# shcV1.net
KiCad netlist of a schematic drawn in EAGLE
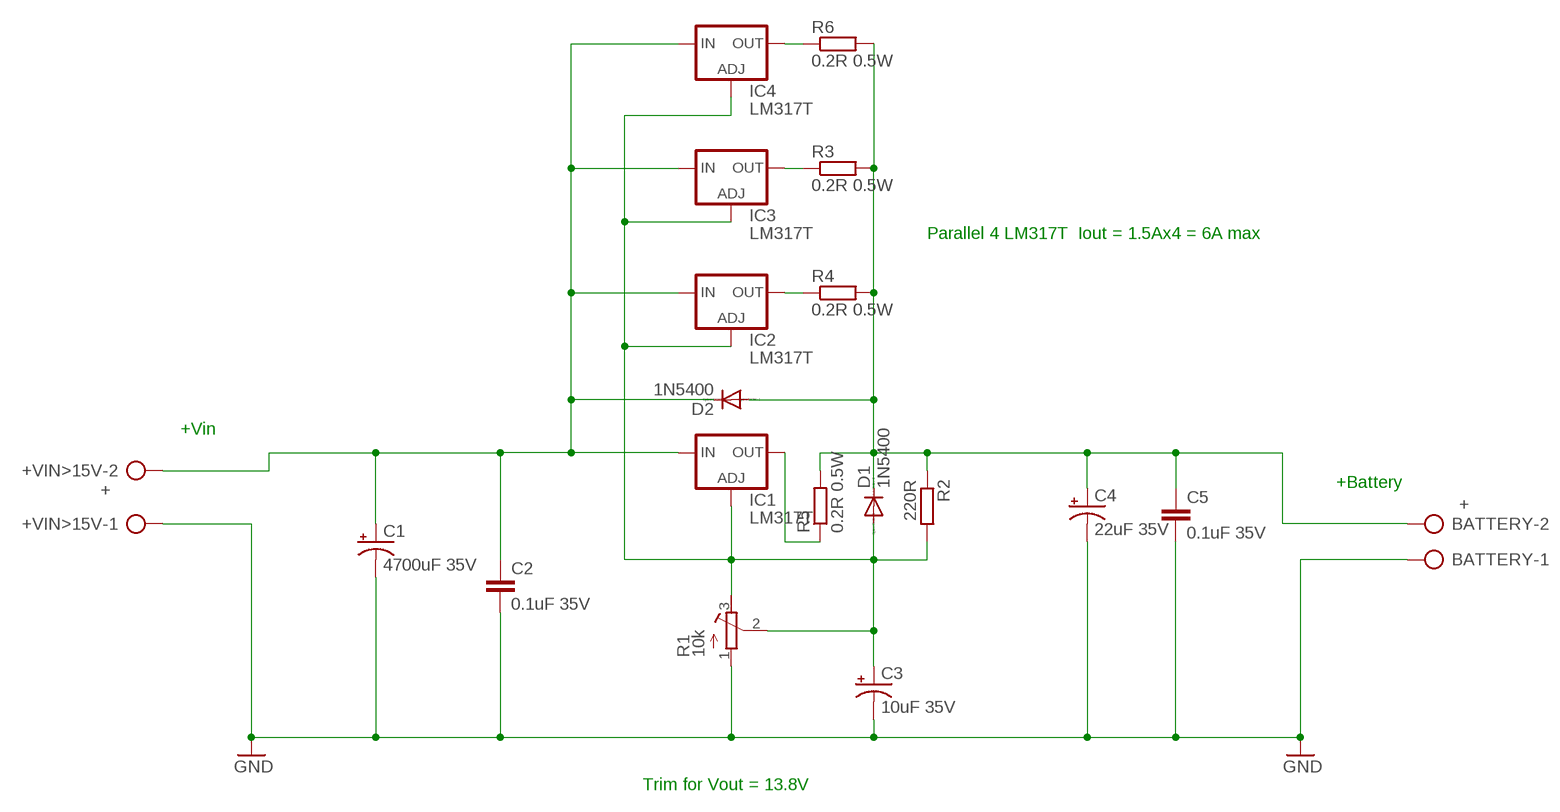
[diagram p0: schematic, sheet 1]

(export (version "E")
  (design (tool "Eeschema 10.0.6"))
  (components
    (comp (ref "+VIN>15V")
      (value "+")
      (footprint "eagle-import:AK300_2")
      (libsource (lib "eagle-import") (part "AK300/2"))
    )
    (comp (ref "BATTERY")
      (value "+")
      (footprint "eagle-import:AK300_2")
      (libsource (lib "eagle-import") (part "AK300/2"))
    )
    (comp (ref "C1")
      (value "4700uF 35V")
      (footprint "eagle-import:E5-13")
      (libsource (lib "eagle-import") (part "CPOL-USE5-13"))
    )
    (comp (ref "C2")
      (value "0.1uF 35V")
      (footprint "eagle-import:C050-024X044")
      (libsource (lib "eagle-import") (part "C-EU050-024X044"))
    )
    (comp (ref "C3")
      (value "10uF 35V")
      (footprint "eagle-import:E5-13")
      (libsource (lib "eagle-import") (part "CPOL-USE5-13"))
    )
    (comp (ref "C4")
      (value "22uF 35V")
      (footprint "eagle-import:E5-13")
      (libsource (lib "eagle-import") (part "CPOL-USE5-13"))
    )
    (comp (ref "C5")
      (value "0.1uF 35V")
      (footprint "eagle-import:C050-024X044")
      (libsource (lib "eagle-import") (part "C-EU050-024X044"))
    )
    (comp (ref "D1")
      (value "1N5400")
      (footprint "eagle-import:DO201-15")
      (libsource (lib "eagle-import") (part "1N5400"))
    )
    (comp (ref "D2")
      (value "1N5400")
      (footprint "eagle-import:DO201-15")
      (libsource (lib "eagle-import") (part "1N5400"))
    )
    (comp (ref "IC1")
      (value "LM317T")
      (footprint "eagle-import:317TS")
      (libsource (lib "eagle-import") (part "LM317TS"))
    )
    (comp (ref "IC2")
      (value "LM317T")
      (footprint "eagle-import:317TS")
      (libsource (lib "eagle-import") (part "LM317TS"))
    )
    (comp (ref "IC3")
      (value "LM317T")
      (footprint "eagle-import:317TS")
      (libsource (lib "eagle-import") (part "LM317TS"))
    )
    (comp (ref "IC4")
      (value "LM317T")
      (footprint "eagle-import:317TS")
      (libsource (lib "eagle-import") (part "LM317TS"))
    )
    (comp (ref "R1")
      (value "10k")
      (footprint "eagle-import:RTRIM64W")
      (libsource (lib "eagle-import") (part "R-TRIMM64W"))
    )
    (comp (ref "R2")
      (value "220R")
      (footprint "eagle-import:0207_10")
      (libsource (lib "eagle-import") (part "R-EU_0207/10"))
    )
    (comp (ref "R3")
      (value "0.2R 0.5W")
      (footprint "eagle-import:0207_10")
      (libsource (lib "eagle-import") (part "R-EU_0207/10"))
    )
    (comp (ref "R4")
      (value "0.2R 0.5W")
      (footprint "eagle-import:0207_10")
      (libsource (lib "eagle-import") (part "R-EU_0207/10"))
    )
    (comp (ref "R5")
      (value "0.2R 0.5W")
      (footprint "eagle-import:0207_10")
      (libsource (lib "eagle-import") (part "R-EU_0207/10"))
    )
    (comp (ref "R6")
      (value "0.2R 0.5W")
      (footprint "eagle-import:0207_10")
      (libsource (lib "eagle-import") (part "R-EU_0207/10"))
    )
  )
  (nets
    (net (code "1") (name "GND") (class "Default")
      (node (ref "+VIN>15V") (pin "1") (pinfunction "KL_1") (pintype "passive"))
      (node (ref "BATTERY") (pin "1") (pinfunction "KL_1") (pintype "passive"))
      (node (ref "C1") (pin "-") (pinfunction "-_-") (pintype "passive"))
      (node (ref "C2") (pin "2") (pinfunction "2_2") (pintype "passive"))
      (node (ref "C3") (pin "-") (pinfunction "-_-") (pintype "passive"))
      (node (ref "C4") (pin "-") (pinfunction "-_-") (pintype "passive"))
      (node (ref "C5") (pin "2") (pinfunction "2_2") (pintype "passive"))
      (node (ref "R1") (pin "1") (pinfunction "A_1") (pintype "passive"))
    )
    (net (code "2") (name "Net-(+VIN>15VB-KL)") (class "Default")
      (node (ref "+VIN>15V") (pin "2") (pinfunction "KL_2") (pintype "passive"))
      (node (ref "C1") (pin "+") (pinfunction "+_+") (pintype "passive"))
      (node (ref "C2") (pin "1") (pinfunction "1_1") (pintype "passive"))
      (node (ref "D2") (pin "C") (pinfunction "C_C") (pintype "passive"))
      (node (ref "IC1") (pin "3") (pinfunction "IN_3") (pintype "input"))
      (node (ref "IC2") (pin "3") (pinfunction "IN_3") (pintype "input"))
      (node (ref "IC3") (pin "3") (pinfunction "IN_3") (pintype "input"))
      (node (ref "IC4") (pin "3") (pinfunction "IN_3") (pintype "input"))
    )
    (net (code "3") (name "Net-(BATTERYB-KL)") (class "Default")
      (node (ref "BATTERY") (pin "2") (pinfunction "KL_2") (pintype "passive"))
      (node (ref "C4") (pin "+") (pinfunction "+_+") (pintype "passive"))
      (node (ref "C5") (pin "1") (pinfunction "1_1") (pintype "passive"))
      (node (ref "D1") (pin "C") (pinfunction "C_C") (pintype "passive"))
      (node (ref "D2") (pin "A") (pinfunction "A_A") (pintype "passive"))
      (node (ref "R2") (pin "1") (pinfunction "1_1") (pintype "passive"))
      (node (ref "R3") (pin "2") (pinfunction "2_2") (pintype "passive"))
      (node (ref "R4") (pin "2") (pinfunction "2_2") (pintype "passive"))
      (node (ref "R5") (pin "2") (pinfunction "2_2") (pintype "passive"))
      (node (ref "R6") (pin "2") (pinfunction "2_2") (pintype "passive"))
    )
    (net (code "4") (name "Net-(IC1-ADJ)") (class "Default")
      (node (ref "C3") (pin "+") (pinfunction "+_+") (pintype "passive"))
      (node (ref "D1") (pin "A") (pinfunction "A_A") (pintype "passive"))
      (node (ref "IC1") (pin "1") (pinfunction "ADJ_1") (pintype "input"))
      (node (ref "IC2") (pin "1") (pinfunction "ADJ_1") (pintype "input"))
      (node (ref "IC3") (pin "1") (pinfunction "ADJ_1") (pintype "input"))
      (node (ref "IC4") (pin "1") (pinfunction "ADJ_1") (pintype "input"))
      (node (ref "R1") (pin "2") (pinfunction "S_2") (pintype "passive"))
      (node (ref "R1") (pin "3") (pinfunction "E_3") (pintype "passive"))
      (node (ref "R2") (pin "2") (pinfunction "2_2") (pintype "passive"))
    )
    (net (code "5") (name "Net-(IC1-OUT)") (class "Default")
      (node (ref "IC1") (pin "2") (pinfunction "OUT_2") (pintype "passive"))
      (node (ref "R5") (pin "1") (pinfunction "1_1") (pintype "passive"))
    )
    (net (code "6") (name "Net-(IC2-OUT)") (class "Default")
      (node (ref "IC2") (pin "2") (pinfunction "OUT_2") (pintype "passive"))
      (node (ref "R4") (pin "1") (pinfunction "1_1") (pintype "passive"))
    )
    (net (code "7") (name "Net-(IC3-OUT)") (class "Default")
      (node (ref "IC3") (pin "2") (pinfunction "OUT_2") (pintype "passive"))
      (node (ref "R3") (pin "1") (pinfunction "1_1") (pintype "passive"))
    )
    (net (code "8") (name "Net-(IC4-OUT)") (class "Default")
      (node (ref "IC4") (pin "2") (pinfunction "OUT_2") (pintype "passive"))
      (node (ref "R6") (pin "1") (pinfunction "1_1") (pintype "passive"))
    )
  )
)
